# Nano_V2_0_20170111.net
KiCad netlist of a schematic drawn in EAGLE
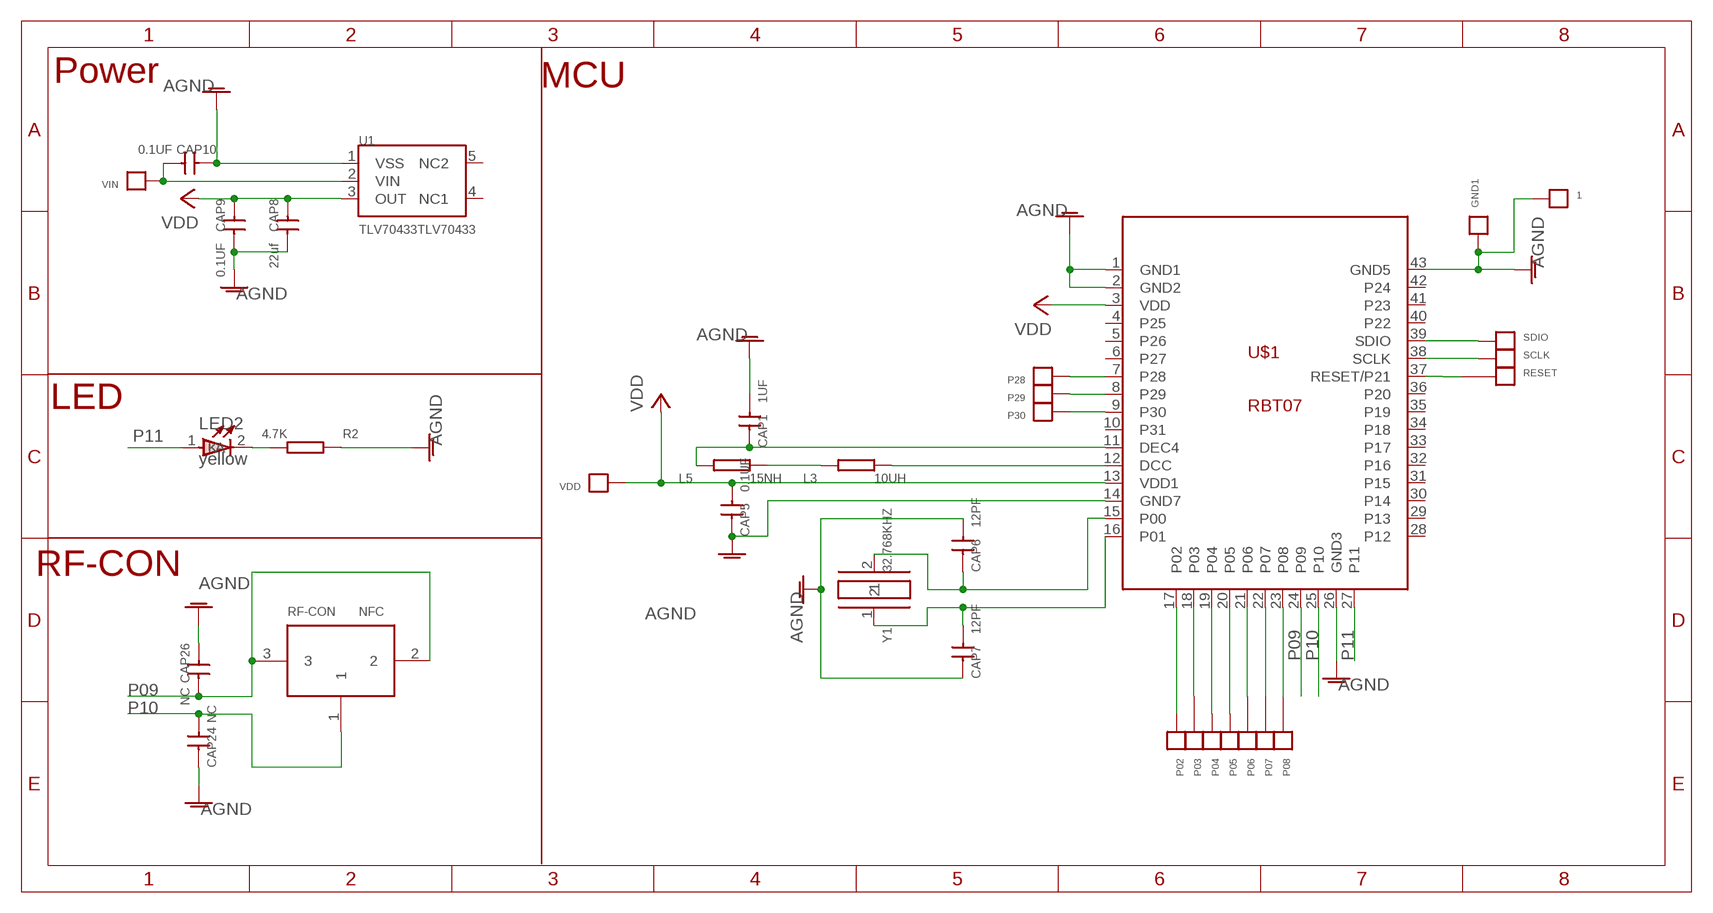
[diagram p0: schematic, sheet 1]

(export (version "E")
  (design (tool "Eeschema 10.0.6"))
  (components
    (comp (ref "1")
      (value "TPDOT_1")
      (footprint "eagle-import:DOT_1")
      (libsource (lib "eagle-import") (part "TPDOT_1"))
    )
    (comp (ref "CAP1")
      (value "1UF")
      (footprint "eagle-import:C-0402")
      (libsource (lib "eagle-import") (part "NANO2_CAP0402"))
    )
    (comp (ref "CAP5")
      (value "0.1UF")
      (footprint "eagle-import:C-0402")
      (libsource (lib "eagle-import") (part "NANO2_CAP0402"))
    )
    (comp (ref "CAP6")
      (value "12PF")
      (footprint "eagle-import:C-0402")
      (libsource (lib "eagle-import") (part "NANO2_CAP0402"))
    )
    (comp (ref "CAP7")
      (value "12PF")
      (footprint "eagle-import:C-0402")
      (libsource (lib "eagle-import") (part "NANO2_CAP0402"))
    )
    (comp (ref "CAP8")
      (value "22uf")
      (footprint "eagle-import:C0805")
      (libsource (lib "eagle-import") (part "NANO2_CAPC0805"))
    )
    (comp (ref "CAP9")
      (value "0.1UF")
      (footprint "eagle-import:C-0402")
      (libsource (lib "eagle-import") (part "NANO2_CAP0402"))
    )
    (comp (ref "CAP10")
      (value "0.1UF")
      (footprint "eagle-import:C-0402")
      (libsource (lib "eagle-import") (part "CAP0402"))
    )
    (comp (ref "CAP24")
      (value "NC")
      (footprint "eagle-import:C-0402")
      (libsource (lib "eagle-import") (part "NANO2_CAP0402"))
    )
    (comp (ref "CAP26")
      (value "NC")
      (footprint "eagle-import:C-0402")
      (libsource (lib "eagle-import") (part "CAP0402"))
    )
    (comp (ref "GND1")
      (value "TPDOT_1.5")
      (footprint "eagle-import:DOT_1.5")
      (libsource (lib "eagle-import") (part "TPDOT_1.5"))
    )
    (comp (ref "L3")
      (value "10UH")
      (footprint "eagle-import:R0603")
      (libsource (lib "eagle-import") (part "RESR0603"))
    )
    (comp (ref "L5")
      (value "15NH")
      (footprint "eagle-import:R0402")
      (libsource (lib "eagle-import") (part "RESR0402"))
    )
    (comp (ref "LED2")
      (value "yellow")
      (footprint "eagle-import:LED0603")
      (libsource (lib "eagle-import") (part "LED"))
    )
    (comp (ref "P02")
      (value "TPDOT_1.5")
      (footprint "eagle-import:DOT_1.5")
      (libsource (lib "eagle-import") (part "TPDOT_1.5"))
    )
    (comp (ref "P03") (value "1P") (footprint "eagle-import:1P") (libsource (lib "eagle-import") (part "1P")))
    (comp (ref "P04")
      (value "TPDOT_1.5")
      (footprint "eagle-import:DOT_1.5")
      (libsource (lib "eagle-import") (part "TPDOT_1.5"))
    )
    (comp (ref "P05")
      (value "TPDOT_1.5")
      (footprint "eagle-import:DOT_1.5")
      (libsource (lib "eagle-import") (part "TPDOT_1.5"))
    )
    (comp (ref "P06") (value "1P") (footprint "eagle-import:1P") (libsource (lib "eagle-import") (part "1P")))
    (comp (ref "P07") (value "1P") (footprint "eagle-import:1P") (libsource (lib "eagle-import") (part "1P")))
    (comp (ref "P08") (value "1P") (footprint "eagle-import:1P") (libsource (lib "eagle-import") (part "1P")))
    (comp (ref "P28")
      (value "TPTPEB")
      (footprint "eagle-import:TPEB")
      (libsource (lib "eagle-import") (part "TPTPEB"))
    )
    (comp (ref "P29")
      (value "TPDOT_1.5")
      (footprint "eagle-import:DOT_1.5")
      (libsource (lib "eagle-import") (part "TPDOT_1.5"))
    )
    (comp (ref "P30")
      (value "TPDOT_1.5")
      (footprint "eagle-import:DOT_1.5")
      (libsource (lib "eagle-import") (part "TPDOT_1.5"))
    )
    (comp (ref "R2")
      (value "4.7K")
      (footprint "eagle-import:R0402")
      (libsource (lib "eagle-import") (part "RESR0402"))
    )
    (comp (ref "RESET")
      (value "1P")
      (footprint "eagle-import:1P")
      (libsource (lib "eagle-import") (part "1P"))
    )
    (comp (ref "RF-CON")
      (value "NFC")
      (footprint "eagle-import:IPEX")
      (libsource (lib "eagle-import") (part "IPEXIPEX"))
    )
    (comp (ref "SCLK")
      (value "TPDOT_1.5")
      (footprint "eagle-import:DOT_1.5")
      (libsource (lib "eagle-import") (part "TPDOT_1.5"))
    )
    (comp (ref "SDIO")
      (value "TPDOT_1.5")
      (footprint "eagle-import:DOT_1.5")
      (libsource (lib "eagle-import") (part "TPDOT_1.5"))
    )
    (comp (ref "U$1")
      (value "RBT07")
      (footprint "eagle-import:RBT07")
      (libsource (lib "eagle-import") (part "RBT07"))
    )
    (comp (ref "U1")
      (value "TLV70433TLV70433")
      (footprint "eagle-import:SOT-23-5")
      (fields (field (name "U1") "TLV70433DBVR"))
      (libsource (lib "eagle-import") (part "TLV70433TLV70433"))
    )
    (comp (ref "VDD")
      (value "TPTPEB")
      (footprint "eagle-import:TPEB")
      (libsource (lib "eagle-import") (part "TPTPEB"))
    )
    (comp (ref "VIN")
      (value "TPDOT_1")
      (footprint "eagle-import:DOT_1")
      (libsource (lib "eagle-import") (part "TPDOT_1"))
    )
    (comp (ref "Y1")
      (value "32.768KHZ")
      (footprint "eagle-import:CRY_3215")
      (libsource (lib "eagle-import") (part "CRY_32153215"))
    )
  )
  (nets
    (net (code "1") (name "/P09") (class "Default")
      (node (ref "CAP26") (pin "1") (pinfunction "1_1") (pintype "bidirectional"))
      (node (ref "RF-CON") (pin "2") (pinfunction "2_2") (pintype "bidirectional"))
      (node (ref "RF-CON") (pin "3") (pinfunction "3_3") (pintype "bidirectional"))
      (node (ref "U$1") (pin "24") (pinfunction "P09_24") (pintype "bidirectional"))
    )
    (net (code "2") (name "/P10") (class "Default")
      (node (ref "CAP24") (pin "1") (pinfunction "1_1") (pintype "bidirectional"))
      (node (ref "RF-CON") (pin "1") (pinfunction "1_1") (pintype "bidirectional"))
      (node (ref "U$1") (pin "25") (pinfunction "P10_25") (pintype "bidirectional"))
    )
    (net (code "3") (name "/P11") (class "Default")
      (node (ref "LED2") (pin "1") (pinfunction "A_1") (pintype "bidirectional"))
      (node (ref "U$1") (pin "27") (pinfunction "P11_27") (pintype "bidirectional"))
    )
    (net (code "4") (name "AGND") (class "Default")
      (node (ref "1") (pin "1") (pinfunction "1_1") (pintype "bidirectional"))
      (node (ref "CAP1") (pin "1") (pinfunction "1_1") (pintype "bidirectional"))
      (node (ref "CAP10") (pin "2") (pinfunction "2_2") (pintype "bidirectional"))
      (node (ref "CAP24") (pin "2") (pinfunction "2_2") (pintype "bidirectional"))
      (node (ref "CAP26") (pin "2") (pinfunction "2_2") (pintype "bidirectional"))
      (node (ref "CAP5") (pin "2") (pinfunction "2_2") (pintype "bidirectional"))
      (node (ref "CAP6") (pin "1") (pinfunction "1_1") (pintype "bidirectional"))
      (node (ref "CAP7") (pin "2") (pinfunction "2_2") (pintype "bidirectional"))
      (node (ref "CAP8") (pin "1") (pinfunction "1_1") (pintype "bidirectional"))
      (node (ref "CAP9") (pin "1") (pinfunction "1_1") (pintype "bidirectional"))
      (node (ref "GND1") (pin "1") (pinfunction "1_1") (pintype "bidirectional"))
      (node (ref "R2") (pin "1") (pinfunction "1_1") (pintype "bidirectional"))
      (node (ref "U$1") (pin "1") (pinfunction "GND1_1") (pintype "bidirectional"))
      (node (ref "U$1") (pin "14") (pinfunction "GND7_14") (pintype "bidirectional"))
      (node (ref "U$1") (pin "2") (pinfunction "GND2_2") (pintype "bidirectional"))
      (node (ref "U$1") (pin "26") (pinfunction "GND3_26") (pintype "bidirectional"))
      (node (ref "U$1") (pin "43") (pinfunction "GND5_43") (pintype "bidirectional"))
      (node (ref "U1") (pin "1") (pinfunction "VSS_1") (pintype "bidirectional"))
    )
    (net (code "5") (name "Net-(L3-Pad1)") (class "Default")
      (node (ref "L3") (pin "1") (pinfunction "1_1") (pintype "bidirectional"))
      (node (ref "L5") (pin "2") (pinfunction "2_2") (pintype "bidirectional"))
    )
    (net (code "6") (name "Net-(LED2-K)") (class "Default")
      (node (ref "LED2") (pin "2") (pinfunction "K_2") (pintype "bidirectional"))
      (node (ref "R2") (pin "2") (pinfunction "2_2") (pintype "bidirectional"))
    )
    (net (code "7") (name "Net-(U$1-DCC)") (class "Default")
      (node (ref "L3") (pin "2") (pinfunction "2_2") (pintype "bidirectional"))
      (node (ref "U$1") (pin "12") (pinfunction "DCC_12") (pintype "bidirectional"))
    )
    (net (code "8") (name "Net-(U$1-DEC4)") (class "Default")
      (node (ref "CAP1") (pin "2") (pinfunction "2_2") (pintype "bidirectional"))
      (node (ref "L5") (pin "1") (pinfunction "1_1") (pintype "bidirectional"))
      (node (ref "U$1") (pin "11") (pinfunction "DEC4_11") (pintype "bidirectional"))
    )
    (net (code "9") (name "Net-(U$1-P00)") (class "Default")
      (node (ref "CAP6") (pin "2") (pinfunction "2_2") (pintype "bidirectional"))
      (node (ref "U$1") (pin "15") (pinfunction "P00_15") (pintype "bidirectional"))
      (node (ref "Y1") (pin "2") (pinfunction "2_2") (pintype "bidirectional"))
    )
    (net (code "10") (name "Net-(U$1-P01)") (class "Default")
      (node (ref "CAP7") (pin "1") (pinfunction "1_1") (pintype "bidirectional"))
      (node (ref "U$1") (pin "16") (pinfunction "P01_16") (pintype "bidirectional"))
      (node (ref "Y1") (pin "1") (pinfunction "1_1") (pintype "bidirectional"))
    )
    (net (code "11") (name "Net-(U$1-P02)") (class "Default")
      (node (ref "P02") (pin "1") (pinfunction "1_1") (pintype "bidirectional"))
      (node (ref "U$1") (pin "17") (pinfunction "P02_17") (pintype "bidirectional"))
    )
    (net (code "12") (name "Net-(U$1-P03)") (class "Default")
      (node (ref "P03") (pin "P$1") (pinfunction "P$1_P$1") (pintype "bidirectional"))
      (node (ref "U$1") (pin "18") (pinfunction "P03_18") (pintype "bidirectional"))
    )
    (net (code "13") (name "Net-(U$1-P04)") (class "Default")
      (node (ref "P04") (pin "1") (pinfunction "1_1") (pintype "bidirectional"))
      (node (ref "U$1") (pin "19") (pinfunction "P04_19") (pintype "bidirectional"))
    )
    (net (code "14") (name "Net-(U$1-P05)") (class "Default")
      (node (ref "P05") (pin "1") (pinfunction "1_1") (pintype "bidirectional"))
      (node (ref "U$1") (pin "20") (pinfunction "P05_20") (pintype "bidirectional"))
    )
    (net (code "15") (name "Net-(U$1-P06)") (class "Default")
      (node (ref "P06") (pin "P$1") (pinfunction "P$1_P$1") (pintype "bidirectional"))
      (node (ref "U$1") (pin "21") (pinfunction "P06_21") (pintype "bidirectional"))
    )
    (net (code "16") (name "Net-(U$1-P07)") (class "Default")
      (node (ref "P07") (pin "P$1") (pinfunction "P$1_P$1") (pintype "bidirectional"))
      (node (ref "U$1") (pin "22") (pinfunction "P07_22") (pintype "bidirectional"))
    )
    (net (code "17") (name "Net-(U$1-P08)") (class "Default")
      (node (ref "P08") (pin "P$1") (pinfunction "P$1_P$1") (pintype "bidirectional"))
      (node (ref "U$1") (pin "23") (pinfunction "P08_23") (pintype "bidirectional"))
    )
    (net (code "18") (name "Net-(U$1-P28)") (class "Default")
      (node (ref "P28") (pin "1") (pinfunction "1_1") (pintype "bidirectional"))
      (node (ref "U$1") (pin "7") (pinfunction "P28_7") (pintype "bidirectional"))
    )
    (net (code "19") (name "Net-(U$1-P29)") (class "Default")
      (node (ref "P29") (pin "1") (pinfunction "1_1") (pintype "bidirectional"))
      (node (ref "U$1") (pin "8") (pinfunction "P29_8") (pintype "bidirectional"))
    )
    (net (code "20") (name "Net-(U$1-P30)") (class "Default")
      (node (ref "P30") (pin "1") (pinfunction "1_1") (pintype "bidirectional"))
      (node (ref "U$1") (pin "9") (pinfunction "P30_9") (pintype "bidirectional"))
    )
    (net (code "21") (name "Net-(U$1-RESET{slash}P21)") (class "Default")
      (node (ref "RESET") (pin "P$1") (pinfunction "P$1_P$1") (pintype "bidirectional"))
      (node (ref "U$1") (pin "37") (pinfunction "RESET/P21_37") (pintype "bidirectional"))
    )
    (net (code "22") (name "Net-(U$1-SCLK)") (class "Default")
      (node (ref "SCLK") (pin "1") (pinfunction "1_1") (pintype "bidirectional"))
      (node (ref "U$1") (pin "38") (pinfunction "SCLK_38") (pintype "bidirectional"))
    )
    (net (code "23") (name "Net-(U$1-SDIO)") (class "Default")
      (node (ref "SDIO") (pin "1") (pinfunction "1_1") (pintype "bidirectional"))
      (node (ref "U$1") (pin "39") (pinfunction "SDIO_39") (pintype "bidirectional"))
    )
    (net (code "24") (name "Net-(U1-VIN)") (class "Default")
      (node (ref "CAP10") (pin "1") (pinfunction "1_1") (pintype "bidirectional"))
      (node (ref "U1") (pin "2") (pinfunction "VIN_2") (pintype "bidirectional"))
      (node (ref "VIN") (pin "1") (pinfunction "1_1") (pintype "bidirectional"))
    )
    (net (code "25") (name "VDD") (class "Default")
      (node (ref "CAP5") (pin "1") (pinfunction "1_1") (pintype "bidirectional"))
      (node (ref "CAP8") (pin "2") (pinfunction "2_2") (pintype "bidirectional"))
      (node (ref "CAP9") (pin "2") (pinfunction "2_2") (pintype "bidirectional"))
      (node (ref "U$1") (pin "13") (pinfunction "VDD1_13") (pintype "bidirectional"))
      (node (ref "U$1") (pin "3") (pinfunction "VDD_3") (pintype "bidirectional"))
      (node (ref "U1") (pin "3") (pinfunction "OUT_3") (pintype "bidirectional"))
      (node (ref "VDD") (pin "1") (pinfunction "1_1") (pintype "bidirectional"))
    )
    (net (code "26") (name "unconnected-(U$1-P12-Pad28)") (class "Default")
      (node (ref "U$1") (pin "28") (pinfunction "P12_28") (pintype "bidirectional"))
    )
    (net (code "27") (name "unconnected-(U$1-P13-Pad29)") (class "Default")
      (node (ref "U$1") (pin "29") (pinfunction "P13_29") (pintype "bidirectional"))
    )
    (net (code "28") (name "unconnected-(U$1-P14-Pad30)") (class "Default")
      (node (ref "U$1") (pin "30") (pinfunction "P14_30") (pintype "bidirectional"))
    )
    (net (code "29") (name "unconnected-(U$1-P15-Pad31)") (class "Default")
      (node (ref "U$1") (pin "31") (pinfunction "P15_31") (pintype "bidirectional"))
    )
    (net (code "30") (name "unconnected-(U$1-P16-Pad32)") (class "Default")
      (node (ref "U$1") (pin "32") (pinfunction "P16_32") (pintype "bidirectional"))
    )
    (net (code "31") (name "unconnected-(U$1-P17-Pad33)") (class "Default")
      (node (ref "U$1") (pin "33") (pinfunction "P17_33") (pintype "bidirectional"))
    )
    (net (code "32") (name "unconnected-(U$1-P18-Pad34)") (class "Default")
      (node (ref "U$1") (pin "34") (pinfunction "P18_34") (pintype "bidirectional"))
    )
    (net (code "33") (name "unconnected-(U$1-P19-Pad35)") (class "Default")
      (node (ref "U$1") (pin "35") (pinfunction "P19_35") (pintype "bidirectional"))
    )
    (net (code "34") (name "unconnected-(U$1-P20-Pad36)") (class "Default")
      (node (ref "U$1") (pin "36") (pinfunction "P20_36") (pintype "bidirectional"))
    )
    (net (code "35") (name "unconnected-(U$1-P22-Pad40)") (class "Default")
      (node (ref "U$1") (pin "40") (pinfunction "P22_40") (pintype "bidirectional"))
    )
    (net (code "36") (name "unconnected-(U$1-P23-Pad41)") (class "Default")
      (node (ref "U$1") (pin "41") (pinfunction "P23_41") (pintype "bidirectional"))
    )
    (net (code "37") (name "unconnected-(U$1-P24-Pad42)") (class "Default")
      (node (ref "U$1") (pin "42") (pinfunction "P24_42") (pintype "bidirectional"))
    )
    (net (code "38") (name "unconnected-(U$1-P25-Pad4)") (class "Default")
      (node (ref "U$1") (pin "4") (pinfunction "P25_4") (pintype "bidirectional"))
    )
    (net (code "39") (name "unconnected-(U$1-P26-Pad5)") (class "Default")
      (node (ref "U$1") (pin "5") (pinfunction "P26_5") (pintype "bidirectional"))
    )
    (net (code "40") (name "unconnected-(U$1-P27-Pad6)") (class "Default")
      (node (ref "U$1") (pin "6") (pinfunction "P27_6") (pintype "bidirectional"))
    )
    (net (code "41") (name "unconnected-(U$1-P31-Pad10)") (class "Default")
      (node (ref "U$1") (pin "10") (pinfunction "P31_10") (pintype "bidirectional"))
    )
    (net (code "42") (name "unconnected-(U1-NC1-Pad4)") (class "Default")
      (node (ref "U1") (pin "4") (pinfunction "NC1_4") (pintype "bidirectional"))
    )
    (net (code "43") (name "unconnected-(U1-NC2-Pad5)") (class "Default")
      (node (ref "U1") (pin "5") (pinfunction "NC2_5") (pintype "bidirectional"))
    )
  )
)
